# Sensor.net
KiCad netlist of a schematic drawn in Altium Designer
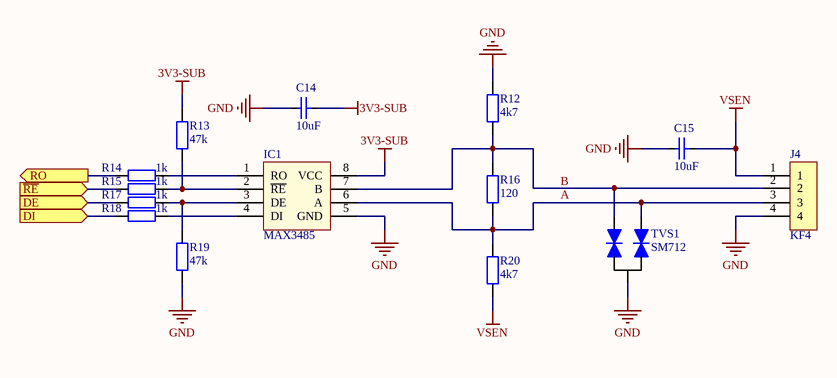
[diagram p0: Sensor.SchDoc]

(export (version "E")
  (design (tool "Eeschema 10.0.6"))
  (components
    (comp (ref "C14")
      (value "10uF")
      (footprint "CAP_0805")
      (description "Capacitor")
      (fields (field (name "PUBLISHER") "Altium Limited"))
      (libsource (lib "My Library") (part "CapSMD"))
    )
    (comp (ref "C15")
      (value "10uF")
      (footprint "CAP_0805")
      (description "Capacitor")
      (fields (field (name "PUBLISHER") "Altium Limited"))
      (libsource (lib "My Library") (part "CapSMD"))
    )
    (comp (ref "IC1")
      (value "MAX3485")
      (footprint "SO-8")
      (description "RS232 - RS485 (Same sn75176)")
      (libsource (lib "My Library") (part "MAX485"))
    )
    (comp (ref "J4")
      (value "KF4")
      (footprint "KF4-5.08")
      (fields
        (field (name "MANUFACTURER") "Würth Elektronik eiSos GmbH")
        (field (name "PARTNO") "691133710004")
        (field (name "CREATED BY") "Baojun Chen")
      )
      (libsource (lib "My Library") (part "KF4"))
    )
    (comp (ref "R12")
      (value "4k7")
      (footprint "RES-SMD-0805")
      (description "Resistor SMD")
      (fields
        (field (name "MANUFACTURER") "Generic Components")
        (field (name "PUBLISHER") "Altium Hobart Technology Centre")
      )
      (libsource (lib "My Library") (part "Resistor - SMD"))
    )
    (comp (ref "R13")
      (value "47k")
      (footprint "RES-SMD-0805")
      (description "Resistor SMD")
      (fields
        (field (name "MANUFACTURER") "Generic Components")
        (field (name "PUBLISHER") "Altium Hobart Technology Centre")
      )
      (libsource (lib "My Library") (part "Resistor - SMD"))
    )
    (comp (ref "R14")
      (value "1k")
      (footprint "RES-SMD-0805")
      (description "Resistor SMD")
      (fields
        (field (name "MANUFACTURER") "Generic Components")
        (field (name "PUBLISHER") "Altium Hobart Technology Centre")
      )
      (libsource (lib "My Library") (part "Resistor - SMD"))
    )
    (comp (ref "R15")
      (value "1k")
      (footprint "RES-SMD-0805")
      (description "Resistor SMD")
      (fields
        (field (name "MANUFACTURER") "Generic Components")
        (field (name "PUBLISHER") "Altium Hobart Technology Centre")
      )
      (libsource (lib "My Library") (part "Resistor - SMD"))
    )
    (comp (ref "R16")
      (value "120")
      (footprint "RES-SMD-0805")
      (description "Resistor SMD")
      (fields
        (field (name "MANUFACTURER") "Generic Components")
        (field (name "PUBLISHER") "Altium Hobart Technology Centre")
      )
      (libsource (lib "My Library") (part "Resistor - SMD"))
    )
    (comp (ref "R17")
      (value "1k")
      (footprint "RES-SMD-0805")
      (description "Resistor SMD")
      (fields
        (field (name "MANUFACTURER") "Generic Components")
        (field (name "PUBLISHER") "Altium Hobart Technology Centre")
      )
      (libsource (lib "My Library") (part "Resistor - SMD"))
    )
    (comp (ref "R18")
      (value "1k")
      (footprint "RES-SMD-0805")
      (description "Resistor SMD")
      (fields
        (field (name "MANUFACTURER") "Generic Components")
        (field (name "PUBLISHER") "Altium Hobart Technology Centre")
      )
      (libsource (lib "My Library") (part "Resistor - SMD"))
    )
    (comp (ref "R19")
      (value "47k")
      (footprint "RES-SMD-0805")
      (description "Resistor SMD")
      (fields
        (field (name "MANUFACTURER") "Generic Components")
        (field (name "PUBLISHER") "Altium Hobart Technology Centre")
      )
      (libsource (lib "My Library") (part "Resistor - SMD"))
    )
    (comp (ref "R20")
      (value "4k7")
      (footprint "RES-SMD-0805")
      (description "Resistor SMD")
      (fields
        (field (name "MANUFACTURER") "Generic Components")
        (field (name "PUBLISHER") "Altium Hobart Technology Centre")
      )
      (libsource (lib "My Library") (part "Resistor - SMD"))
    )
    (comp (ref "TVS1")
      (value "SM712")
      (footprint "SOT23")
      (description "BAV70")
      (libsource (lib "My Library") (part "BAV70"))
    )
  )
  (nets
    (net (code "1") (name "/A") (class "Default")
      (node (ref "IC1") (pin "6") (pinfunction "A_6") (pintype "passive"))
      (node (ref "J4") (pin "3") (pinfunction "3_3") (pintype "passive"))
      (node (ref "R16") (pin "1") (pinfunction "1_1") (pintype "passive"))
      (node (ref "R20") (pin "2") (pinfunction "2_2") (pintype "passive"))
      (node (ref "TVS1") (pin "1") (pinfunction "A_1") (pintype "passive"))
    )
    (net (code "3") (name "/DE") (class "Default")
      (node (ref "R17") (pin "2") (pinfunction "2_2") (pintype "passive"))
    )
    (net (code "4") (name "/DI") (class "Default")
      (node (ref "R18") (pin "2") (pinfunction "2_2") (pintype "passive"))
    )
    (net (code "5") (name "/RO") (class "Default")
      (node (ref "R14") (pin "2") (pinfunction "2_2") (pintype "passive"))
    )
    (net (code "6") (name "/~{RE}") (class "Default")
      (node (ref "R15") (pin "2") (pinfunction "2_2") (pintype "passive"))
    )
    (net (code "7") (name "3V3-SUB") (class "Default")
      (node (ref "C14") (pin "2") (pinfunction "2_2") (pintype "passive"))
      (node (ref "IC1") (pin "8") (pinfunction "VCC_8") (pintype "passive"))
      (node (ref "R13") (pin "1") (pinfunction "1_1") (pintype "passive"))
    )
    (net (code "8") (name "GND") (class "Default")
      (node (ref "C14") (pin "1") (pinfunction "1_1") (pintype "passive"))
      (node (ref "C15") (pin "1") (pinfunction "1_1") (pintype "passive"))
      (node (ref "IC1") (pin "5") (pinfunction "GND_5") (pintype "passive"))
      (node (ref "J4") (pin "4") (pinfunction "4_4") (pintype "passive"))
      (node (ref "R12") (pin "2") (pinfunction "2_2") (pintype "passive"))
      (node (ref "R19") (pin "2") (pinfunction "2_2") (pintype "passive"))
      (node (ref "TVS1") (pin "3") (pinfunction "K_3") (pintype "passive"))
    )
    (net (code "9") (name "Net-(IC1-B)") (class "Default")
      (node (ref "IC1") (pin "7") (pinfunction "B_7") (pintype "passive"))
      (node (ref "J4") (pin "2") (pinfunction "2_2") (pintype "passive"))
      (node (ref "R12") (pin "1") (pinfunction "1_1") (pintype "passive"))
      (node (ref "R16") (pin "2") (pinfunction "2_2") (pintype "passive"))
      (node (ref "TVS1") (pin "2") (pinfunction "A_2") (pintype "passive"))
    )
    (net (code "10") (name "Net-(IC1-DE)") (class "Default")
      (node (ref "IC1") (pin "3") (pinfunction "DE_3") (pintype "passive"))
      (node (ref "R17") (pin "1") (pinfunction "1_1") (pintype "passive"))
      (node (ref "R19") (pin "1") (pinfunction "1_1") (pintype "passive"))
    )
    (net (code "11") (name "Net-(IC1-DI)") (class "Default")
      (node (ref "IC1") (pin "4") (pinfunction "DI_4") (pintype "passive"))
      (node (ref "R18") (pin "1") (pinfunction "1_1") (pintype "passive"))
    )
    (net (code "12") (name "Net-(IC1-RO)") (class "Default")
      (node (ref "IC1") (pin "1") (pinfunction "RO_1") (pintype "passive"))
      (node (ref "R14") (pin "1") (pinfunction "1_1") (pintype "passive"))
    )
    (net (code "13") (name "Net-(IC1-~{RE})") (class "Default")
      (node (ref "IC1") (pin "2") (pinfunction "~{RE}_2") (pintype "passive"))
      (node (ref "R13") (pin "2") (pinfunction "2_2") (pintype "passive"))
      (node (ref "R15") (pin "1") (pinfunction "1_1") (pintype "passive"))
    )
    (net (code "14") (name "VSEN") (class "Default")
      (node (ref "C15") (pin "2") (pinfunction "2_2") (pintype "passive"))
      (node (ref "J4") (pin "1") (pinfunction "1_1") (pintype "passive"))
      (node (ref "R20") (pin "1") (pinfunction "1_1") (pintype "passive"))
    )
  )
)
